# OptoRelayX2.net
KiCad netlist of a schematic drawn in EAGLE
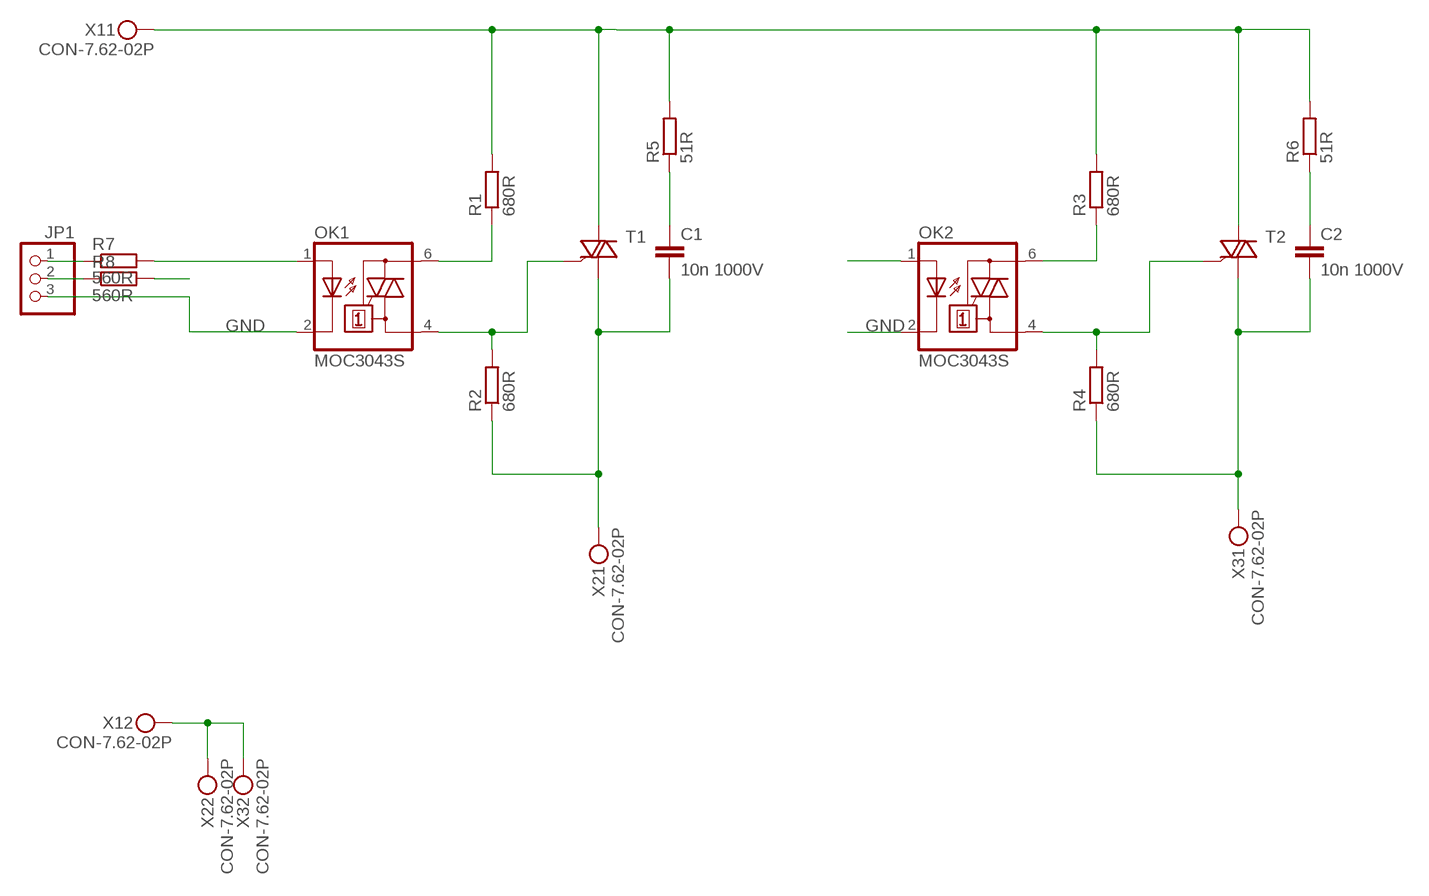
[diagram p0: schematic, sheet 1]

(export (version "E")
  (design (tool "Eeschema 10.0.6"))
  (components
    (comp (ref "C1")
      (value "10n 1000V")
      (footprint "eagle-import:C050-024X044")
      (libsource (lib "eagle-import") (part "CAP_C50-024X044"))
    )
    (comp (ref "C2")
      (value "10n 1000V")
      (footprint "eagle-import:C050-024X044")
      (libsource (lib "eagle-import") (part "CAP_C50-024X044"))
    )
    (comp (ref "JP1")
      (value "PINHD-1X3")
      (footprint "eagle-import:1X03")
      (libsource (lib "eagle-import") (part "PINHD-1X3"))
    )
    (comp (ref "OK1")
      (value "MOC3043S")
      (footprint "eagle-import:DIL6-SMD")
      (fields (field (name "MF") "FAIRCHILD SEMICONDUCTOR") (field (name "MPN") "MOC3043SM"))
      (libsource (lib "eagle-import") (part "MOC30S43"))
    )
    (comp (ref "OK2")
      (value "MOC3043S")
      (footprint "eagle-import:DIL6-SMD")
      (fields (field (name "MF") "FAIRCHILD SEMICONDUCTOR") (field (name "MPN") "MOC3043SM"))
      (libsource (lib "eagle-import") (part "MOC30S43"))
    )
    (comp (ref "R1")
      (value "680R")
      (footprint "eagle-import:MF-05")
      (libsource (lib "eagle-import") (part "R_MF-05"))
    )
    (comp (ref "R2")
      (value "680R")
      (footprint "eagle-import:MF-05")
      (libsource (lib "eagle-import") (part "R_MF-05"))
    )
    (comp (ref "R3")
      (value "680R")
      (footprint "eagle-import:MF-05")
      (libsource (lib "eagle-import") (part "R_MF-05"))
    )
    (comp (ref "R4")
      (value "680R")
      (footprint "eagle-import:MF-05")
      (libsource (lib "eagle-import") (part "R_MF-05"))
    )
    (comp (ref "R5")
      (value "51R")
      (footprint "eagle-import:MF-2")
      (libsource (lib "eagle-import") (part "R_MF-2"))
    )
    (comp (ref "R6")
      (value "51R")
      (footprint "eagle-import:MF-2")
      (libsource (lib "eagle-import") (part "R_MF-2"))
    )
    (comp (ref "R7")
      (value "560R")
      (footprint "eagle-import:R0805")
      (libsource (lib "eagle-import") (part "R_0805"))
    )
    (comp (ref "R8")
      (value "560R")
      (footprint "eagle-import:R0805")
      (libsource (lib "eagle-import") (part "R_0805"))
    )
    (comp (ref "T1")
      (value "TRIAC")
      (footprint "eagle-import:DPAK")
      (libsource (lib "eagle-import") (part "TRIAC"))
    )
    (comp (ref "T2")
      (value "TRIAC")
      (footprint "eagle-import:DPAK")
      (libsource (lib "eagle-import") (part "TRIAC"))
    )
    (comp (ref "X1")
      (value "CON-7.62-02P")
      (footprint "eagle-import:KF25C-7.62-02P-13")
      (libsource (lib "eagle-import") (part "CON-7.62-02P"))
    )
    (comp (ref "X2")
      (value "CON-7.62-02P")
      (footprint "eagle-import:KF25C-7.62-02P-13")
      (libsource (lib "eagle-import") (part "CON-7.62-02P"))
    )
    (comp (ref "X3")
      (value "CON-7.62-02P")
      (footprint "eagle-import:KF25C-7.62-02P-13")
      (libsource (lib "eagle-import") (part "CON-7.62-02P"))
    )
  )
  (nets
    (net (code "1") (name "/GND") (class "Default")
      (node (ref "JP1") (pin "3") (pinfunction "3_3") (pintype "passive"))
      (node (ref "OK1") (pin "2") (pinfunction "C_2") (pintype "passive"))
      (node (ref "OK2") (pin "2") (pinfunction "C_2") (pintype "passive"))
    )
    (net (code "2") (name "/N$14") (class "Default")
      (node (ref "OK2") (pin "1") (pinfunction "A_1") (pintype "passive"))
      (node (ref "R8") (pin "2") (pinfunction "2_2") (pintype "passive"))
    )
    (net (code "3") (name "Net-(C1-Pad1)") (class "Default")
      (node (ref "C1") (pin "1") (pinfunction "1_1") (pintype "passive"))
      (node (ref "R5") (pin "1") (pinfunction "1_1") (pintype "passive"))
    )
    (net (code "4") (name "Net-(C2-Pad1)") (class "Default")
      (node (ref "C2") (pin "1") (pinfunction "1_1") (pintype "passive"))
      (node (ref "R6") (pin "1") (pinfunction "1_1") (pintype "passive"))
    )
    (net (code "5") (name "Net-(JP1-Pad1)") (class "Default")
      (node (ref "JP1") (pin "1") (pinfunction "1_1") (pintype "passive"))
      (node (ref "R7") (pin "1") (pinfunction "1_1") (pintype "passive"))
    )
    (net (code "6") (name "Net-(JP1-Pad2)") (class "Default")
      (node (ref "JP1") (pin "2") (pinfunction "2_2") (pintype "passive"))
      (node (ref "R8") (pin "1") (pinfunction "1_1") (pintype "passive"))
    )
    (net (code "7") (name "Net-(OK1-A)") (class "Default")
      (node (ref "OK1") (pin "1") (pinfunction "A_1") (pintype "passive"))
      (node (ref "R7") (pin "2") (pinfunction "2_2") (pintype "passive"))
    )
    (net (code "8") (name "Net-(OK1-A1)") (class "Default")
      (node (ref "OK1") (pin "4") (pinfunction "A1_4") (pintype "passive"))
      (node (ref "R2") (pin "2") (pinfunction "2_2") (pintype "passive"))
      (node (ref "T1") (pin "S") (pinfunction "G_S") (pintype "passive"))
    )
    (net (code "9") (name "Net-(OK1-A2)") (class "Default")
      (node (ref "OK1") (pin "6") (pinfunction "A2_6") (pintype "passive"))
      (node (ref "R1") (pin "1") (pinfunction "1_1") (pintype "passive"))
    )
    (net (code "10") (name "Net-(OK2-A1)") (class "Default")
      (node (ref "OK2") (pin "4") (pinfunction "A1_4") (pintype "passive"))
      (node (ref "R4") (pin "2") (pinfunction "2_2") (pintype "passive"))
      (node (ref "T2") (pin "S") (pinfunction "G_S") (pintype "passive"))
    )
    (net (code "11") (name "Net-(OK2-A2)") (class "Default")
      (node (ref "OK2") (pin "6") (pinfunction "A2_6") (pintype "passive"))
      (node (ref "R3") (pin "1") (pinfunction "1_1") (pintype "passive"))
    )
    (net (code "12") (name "Net-(T1-A1)") (class "Default")
      (node (ref "C1") (pin "2") (pinfunction "2_2") (pintype "passive"))
      (node (ref "R2") (pin "1") (pinfunction "1_1") (pintype "passive"))
      (node (ref "T1") (pin "G") (pinfunction "A1_G") (pintype "passive"))
      (node (ref "X2") (pin "P$1") (pinfunction "KL_P$1") (pintype "passive"))
    )
    (net (code "13") (name "Net-(T1-A2)") (class "Default")
      (node (ref "R1") (pin "2") (pinfunction "2_2") (pintype "passive"))
      (node (ref "R3") (pin "2") (pinfunction "2_2") (pintype "passive"))
      (node (ref "R5") (pin "2") (pinfunction "2_2") (pintype "passive"))
      (node (ref "R6") (pin "2") (pinfunction "2_2") (pintype "passive"))
      (node (ref "T1") (pin "D") (pinfunction "A2_D") (pintype "passive"))
      (node (ref "T2") (pin "D") (pinfunction "A2_D") (pintype "passive"))
      (node (ref "X1") (pin "P$1") (pinfunction "KL_P$1") (pintype "passive"))
    )
    (net (code "14") (name "Net-(T2-A1)") (class "Default")
      (node (ref "C2") (pin "2") (pinfunction "2_2") (pintype "passive"))
      (node (ref "R4") (pin "1") (pinfunction "1_1") (pintype "passive"))
      (node (ref "T2") (pin "G") (pinfunction "A1_G") (pintype "passive"))
      (node (ref "X3") (pin "P$1") (pinfunction "KL_P$1") (pintype "passive"))
    )
    (net (code "15") (name "Net-(X1B-KL)") (class "Default")
      (node (ref "X1") (pin "P$2") (pinfunction "KL_P$2") (pintype "passive"))
      (node (ref "X2") (pin "P$2") (pinfunction "KL_P$2") (pintype "passive"))
      (node (ref "X3") (pin "P$2") (pinfunction "KL_P$2") (pintype "passive"))
    )
  )
)
